# usb.net
KiCad netlist of a schematic drawn in EAGLE
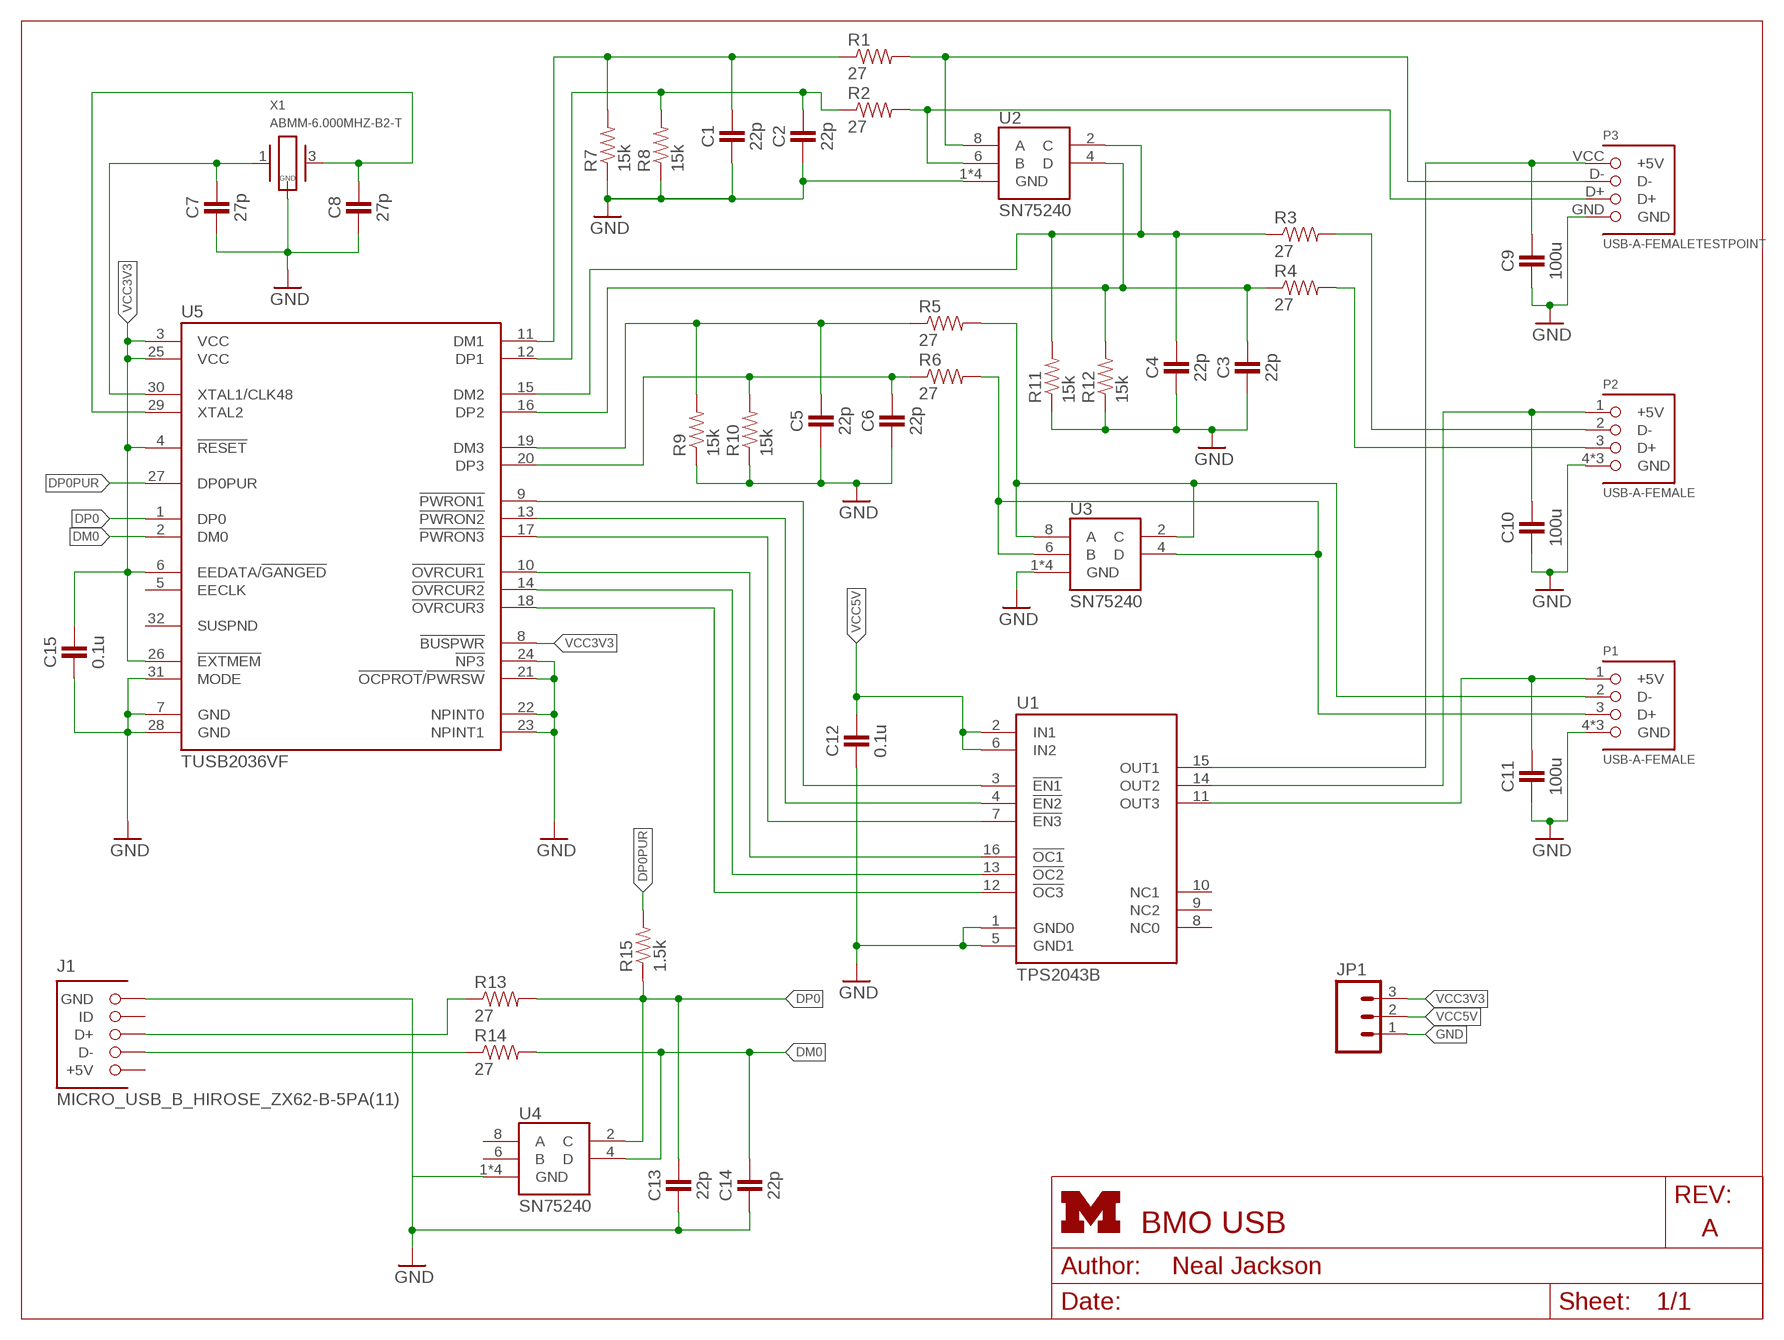
[diagram p0: schematic, sheet 1]

(export (version "E")
  (design (tool "Eeschema 10.0.6"))
  (components
    (comp (ref "C1")
      (value "22p")
      (footprint "eagle-import:0402_CAP")
      (libsource (lib "eagle-import") (part "CAPACITOR"))
    )
    (comp (ref "C2")
      (value "22p")
      (footprint "eagle-import:0402_CAP")
      (libsource (lib "eagle-import") (part "CAPACITOR"))
    )
    (comp (ref "C3")
      (value "22p")
      (footprint "eagle-import:0402_CAP")
      (libsource (lib "eagle-import") (part "CAPACITOR"))
    )
    (comp (ref "C4")
      (value "22p")
      (footprint "eagle-import:0402_CAP")
      (libsource (lib "eagle-import") (part "CAPACITOR"))
    )
    (comp (ref "C5")
      (value "22p")
      (footprint "eagle-import:0402_CAP")
      (libsource (lib "eagle-import") (part "CAPACITOR"))
    )
    (comp (ref "C6")
      (value "22p")
      (footprint "eagle-import:0402_CAP")
      (libsource (lib "eagle-import") (part "CAPACITOR"))
    )
    (comp (ref "C7")
      (value "27p")
      (footprint "eagle-import:0402_CAP")
      (libsource (lib "eagle-import") (part "CAPACITOR"))
    )
    (comp (ref "C8")
      (value "27p")
      (footprint "eagle-import:0402_CAP")
      (libsource (lib "eagle-import") (part "CAPACITOR"))
    )
    (comp (ref "C9")
      (value "100u")
      (footprint "eagle-import:0402_CAP")
      (libsource (lib "eagle-import") (part "CAPACITOR"))
    )
    (comp (ref "C10")
      (value "100u")
      (footprint "eagle-import:0402_CAP")
      (libsource (lib "eagle-import") (part "CAPACITOR"))
    )
    (comp (ref "C11")
      (value "100u")
      (footprint "eagle-import:0402_CAP")
      (libsource (lib "eagle-import") (part "CAPACITOR"))
    )
    (comp (ref "C12")
      (value "0.1u")
      (footprint "eagle-import:0402_CAP")
      (libsource (lib "eagle-import") (part "CAPACITOR"))
    )
    (comp (ref "C13")
      (value "22p")
      (footprint "eagle-import:0402_CAP")
      (libsource (lib "eagle-import") (part "CAPACITOR"))
    )
    (comp (ref "C14")
      (value "22p")
      (footprint "eagle-import:0402_CAP")
      (libsource (lib "eagle-import") (part "CAPACITOR"))
    )
    (comp (ref "C15")
      (value "0.1u")
      (footprint "eagle-import:0402_CAP")
      (libsource (lib "eagle-import") (part "CAPACITOR"))
    )
    (comp (ref "J1")
      (value "MICRO_USB_B_HIROSE_ZX62-B-5PA(11)")
      (footprint "eagle-import:USB_MICRO_B-HIROSE-ZX62-B-5PA(11)")
      (libsource (lib "eagle-import") (part "MICRO_USB_B_HIROSE_ZX62-B-5PA(11)"))
    )
    (comp (ref "JP1")
      (value "M03PTH")
      (footprint "eagle-import:1X03")
      (libsource (lib "eagle-import") (part "M03PTH"))
    )
    (comp (ref "P1")
      (value "USB-A-FEMALE")
      (footprint "eagle-import:87583-3010RPALF")
      (libsource (lib "eagle-import") (part "USB-A-FEMALE"))
    )
    (comp (ref "P2")
      (value "USB-A-FEMALE")
      (footprint "eagle-import:87583-3010RPALF")
      (libsource (lib "eagle-import") (part "USB-A-FEMALE"))
    )
    (comp (ref "P3")
      (value "USB-A-FEMALETESTPOINT")
      (footprint "eagle-import:USB-A-TESTPOINT")
      (libsource (lib "eagle-import") (part "USB-A-FEMALETESTPOINT"))
    )
    (comp (ref "R1")
      (value "27")
      (footprint "eagle-import:0402_RES")
      (libsource (lib "eagle-import") (part "RESISTOR0402_RES"))
    )
    (comp (ref "R2")
      (value "27")
      (footprint "eagle-import:0402_RES")
      (libsource (lib "eagle-import") (part "RESISTOR0402_RES"))
    )
    (comp (ref "R3")
      (value "27")
      (footprint "eagle-import:0402_RES")
      (libsource (lib "eagle-import") (part "RESISTOR0402_RES"))
    )
    (comp (ref "R4")
      (value "27")
      (footprint "eagle-import:0402_RES")
      (libsource (lib "eagle-import") (part "RESISTOR0402_RES"))
    )
    (comp (ref "R5")
      (value "27")
      (footprint "eagle-import:0402_RES")
      (libsource (lib "eagle-import") (part "RESISTOR0402_RES"))
    )
    (comp (ref "R6")
      (value "27")
      (footprint "eagle-import:0402_RES")
      (libsource (lib "eagle-import") (part "RESISTOR0402_RES"))
    )
    (comp (ref "R7")
      (value "15k")
      (footprint "eagle-import:0402_RES")
      (libsource (lib "eagle-import") (part "RESISTOR0402_RES"))
    )
    (comp (ref "R8")
      (value "15k")
      (footprint "eagle-import:0402_RES")
      (libsource (lib "eagle-import") (part "RESISTOR0402_RES"))
    )
    (comp (ref "R9")
      (value "15k")
      (footprint "eagle-import:0402_RES")
      (libsource (lib "eagle-import") (part "RESISTOR0402_RES"))
    )
    (comp (ref "R10")
      (value "15k")
      (footprint "eagle-import:0402_RES")
      (libsource (lib "eagle-import") (part "RESISTOR0402_RES"))
    )
    (comp (ref "R11")
      (value "15k")
      (footprint "eagle-import:0402_RES")
      (libsource (lib "eagle-import") (part "RESISTOR0402_RES"))
    )
    (comp (ref "R12")
      (value "15k")
      (footprint "eagle-import:0402_RES")
      (libsource (lib "eagle-import") (part "RESISTOR0402_RES"))
    )
    (comp (ref "R13")
      (value "27")
      (footprint "eagle-import:0402_RES")
      (libsource (lib "eagle-import") (part "RESISTOR0402_RES"))
    )
    (comp (ref "R14")
      (value "27")
      (footprint "eagle-import:0402_RES")
      (libsource (lib "eagle-import") (part "RESISTOR0402_RES"))
    )
    (comp (ref "R15")
      (value "1.5k")
      (footprint "eagle-import:0402_RES")
      (libsource (lib "eagle-import") (part "RESISTOR0402_RES"))
    )
    (comp (ref "U1")
      (value "TPS2043B")
      (footprint "eagle-import:SO16")
      (libsource (lib "eagle-import") (part "TPS2043B"))
    )
    (comp (ref "U2")
      (value "SN75240")
      (footprint "eagle-import:TSSOP8")
      (libsource (lib "eagle-import") (part "SN75240"))
    )
    (comp (ref "U3")
      (value "SN75240")
      (footprint "eagle-import:TSSOP8")
      (libsource (lib "eagle-import") (part "SN75240"))
    )
    (comp (ref "U4")
      (value "SN75240")
      (footprint "eagle-import:TSSOP8")
      (libsource (lib "eagle-import") (part "SN75240"))
    )
    (comp (ref "U5")
      (value "TUSB2036VF")
      (footprint "eagle-import:VF_S-PQFP-G32")
      (libsource (lib "eagle-import") (part "TUSB2036VF"))
    )
    (comp (ref "X1")
      (value "ABMM-6.000MHZ-B2-T")
      (footprint "eagle-import:ABMM-6.000MHZ-B2-T")
      (libsource (lib "eagle-import") (part "ABMM-6.000MHZ-B2-T"))
    )
  )
  (nets
    (net (code "1") (name "DM0") (class "Default")
      (node (ref "C14") (pin "1") (pinfunction "1_1") (pintype "bidirectional"))
      (node (ref "R14") (pin "2") (pinfunction "2_2") (pintype "passive"))
      (node (ref "U4") (pin "4") (pinfunction "D_4") (pintype "bidirectional"))
      (node (ref "U5") (pin "2") (pinfunction "DM0_2") (pintype "bidirectional"))
    )
    (net (code "2") (name "DP0") (class "Default")
      (node (ref "C13") (pin "1") (pinfunction "1_1") (pintype "bidirectional"))
      (node (ref "R13") (pin "2") (pinfunction "2_2") (pintype "passive"))
      (node (ref "R15") (pin "1") (pinfunction "1_1") (pintype "passive"))
      (node (ref "U4") (pin "2") (pinfunction "C_2") (pintype "bidirectional"))
      (node (ref "U5") (pin "1") (pinfunction "DP0_1") (pintype "bidirectional"))
    )
    (net (code "3") (name "DP0PUR") (class "Default")
      (node (ref "R15") (pin "2") (pinfunction "2_2") (pintype "passive"))
      (node (ref "U5") (pin "27") (pinfunction "DP0PUR_27") (pintype "output"))
    )
    (net (code "4") (name "GND") (class "Default")
      (node (ref "C1") (pin "2") (pinfunction "2_2") (pintype "bidirectional"))
      (node (ref "C10") (pin "2") (pinfunction "2_2") (pintype "bidirectional"))
      (node (ref "C11") (pin "2") (pinfunction "2_2") (pintype "bidirectional"))
      (node (ref "C12") (pin "2") (pinfunction "2_2") (pintype "bidirectional"))
      (node (ref "C13") (pin "2") (pinfunction "2_2") (pintype "bidirectional"))
      (node (ref "C14") (pin "2") (pinfunction "2_2") (pintype "bidirectional"))
      (node (ref "C15") (pin "2") (pinfunction "2_2") (pintype "bidirectional"))
      (node (ref "C2") (pin "2") (pinfunction "2_2") (pintype "bidirectional"))
      (node (ref "C3") (pin "2") (pinfunction "2_2") (pintype "bidirectional"))
      (node (ref "C4") (pin "2") (pinfunction "2_2") (pintype "bidirectional"))
      (node (ref "C5") (pin "2") (pinfunction "2_2") (pintype "bidirectional"))
      (node (ref "C6") (pin "2") (pinfunction "2_2") (pintype "bidirectional"))
      (node (ref "C7") (pin "2") (pinfunction "2_2") (pintype "bidirectional"))
      (node (ref "C8") (pin "2") (pinfunction "2_2") (pintype "bidirectional"))
      (node (ref "C9") (pin "2") (pinfunction "2_2") (pintype "bidirectional"))
      (node (ref "J1") (pin "5") (pinfunction "GND_5") (pintype "bidirectional"))
      (node (ref "JP1") (pin "1") (pinfunction "1_1") (pintype "passive"))
      (node (ref "P1") (pin "4") (pinfunction "GND_4") (pintype "bidirectional"))
      (node (ref "P1") (pin "P$1") (pinfunction "GND_P$1") (pintype "bidirectional"))
      (node (ref "P1") (pin "P$2") (pinfunction "GND_P$2") (pintype "bidirectional"))
      (node (ref "P2") (pin "4") (pinfunction "GND_4") (pintype "bidirectional"))
      (node (ref "P2") (pin "P$1") (pinfunction "GND_P$1") (pintype "bidirectional"))
      (node (ref "P2") (pin "P$2") (pinfunction "GND_P$2") (pintype "bidirectional"))
      (node (ref "P3") (pin "GND") (pinfunction "GND_GND") (pintype "bidirectional"))
      (node (ref "R10") (pin "1") (pinfunction "1_1") (pintype "passive"))
      (node (ref "R11") (pin "1") (pinfunction "1_1") (pintype "passive"))
      (node (ref "R12") (pin "1") (pinfunction "1_1") (pintype "passive"))
      (node (ref "R7") (pin "1") (pinfunction "1_1") (pintype "passive"))
      (node (ref "R8") (pin "1") (pinfunction "1_1") (pintype "passive"))
      (node (ref "R9") (pin "1") (pinfunction "1_1") (pintype "passive"))
      (node (ref "U1") (pin "1") (pinfunction "GND0_1") (pintype "bidirectional"))
      (node (ref "U1") (pin "5") (pinfunction "GND1_5") (pintype "bidirectional"))
      (node (ref "U2") (pin "1") (pinfunction "GND_1") (pintype "bidirectional"))
      (node (ref "U2") (pin "3") (pinfunction "GND_3") (pintype "bidirectional"))
      (node (ref "U2") (pin "5") (pinfunction "GND_5") (pintype "bidirectional"))
      (node (ref "U2") (pin "7") (pinfunction "GND_7") (pintype "bidirectional"))
      (node (ref "U3") (pin "1") (pinfunction "GND_1") (pintype "bidirectional"))
      (node (ref "U3") (pin "3") (pinfunction "GND_3") (pintype "bidirectional"))
      (node (ref "U3") (pin "5") (pinfunction "GND_5") (pintype "bidirectional"))
      (node (ref "U3") (pin "7") (pinfunction "GND_7") (pintype "bidirectional"))
      (node (ref "U4") (pin "1") (pinfunction "GND_1") (pintype "bidirectional"))
      (node (ref "U4") (pin "3") (pinfunction "GND_3") (pintype "bidirectional"))
      (node (ref "U4") (pin "5") (pinfunction "GND_5") (pintype "bidirectional"))
      (node (ref "U4") (pin "7") (pinfunction "GND_7") (pintype "bidirectional"))
      (node (ref "U5") (pin "21") (pinfunction "~{OCPROT}/~{PWRSW}_21") (pintype "input"))
      (node (ref "U5") (pin "22") (pinfunction "NPINT0_22") (pintype "input"))
      (node (ref "U5") (pin "23") (pinfunction "NPINT1_23") (pintype "input"))
      (node (ref "U5") (pin "24") (pinfunction "~{NP3}_24") (pintype "input"))
      (node (ref "U5") (pin "28") (pinfunction "GND_28") (pintype "power_in"))
      (node (ref "U5") (pin "31") (pinfunction "MODE_31") (pintype "input"))
      (node (ref "U5") (pin "7") (pinfunction "GND_7") (pintype "power_in"))
      (node (ref "X1") (pin "2") (pinfunction "GND_2") (pintype "bidirectional"))
      (node (ref "X1") (pin "4") (pinfunction "GND_4") (pintype "bidirectional"))
    )
    (net (code "5") (name "Net-(J1-D+)") (class "Default")
      (node (ref "J1") (pin "3") (pinfunction "D+_3") (pintype "bidirectional"))
      (node (ref "R13") (pin "1") (pinfunction "1_1") (pintype "passive"))
    )
    (net (code "6") (name "Net-(J1-D-)") (class "Default")
      (node (ref "J1") (pin "2") (pinfunction "D-_2") (pintype "bidirectional"))
      (node (ref "R14") (pin "1") (pinfunction "1_1") (pintype "passive"))
    )
    (net (code "7") (name "Net-(P1-+5V)") (class "Default")
      (node (ref "C11") (pin "1") (pinfunction "1_1") (pintype "bidirectional"))
      (node (ref "P1") (pin "1") (pinfunction "+5V_1") (pintype "bidirectional"))
      (node (ref "U1") (pin "11") (pinfunction "OUT3_11") (pintype "bidirectional"))
    )
    (net (code "8") (name "Net-(P1-D+)") (class "Default")
      (node (ref "P1") (pin "3") (pinfunction "D+_3") (pintype "bidirectional"))
      (node (ref "R6") (pin "2") (pinfunction "2_2") (pintype "passive"))
      (node (ref "U3") (pin "4") (pinfunction "D_4") (pintype "bidirectional"))
      (node (ref "U3") (pin "6") (pinfunction "B_6") (pintype "bidirectional"))
    )
    (net (code "9") (name "Net-(P1-D-)") (class "Default")
      (node (ref "P1") (pin "2") (pinfunction "D-_2") (pintype "bidirectional"))
      (node (ref "R5") (pin "2") (pinfunction "2_2") (pintype "passive"))
      (node (ref "U3") (pin "2") (pinfunction "C_2") (pintype "bidirectional"))
      (node (ref "U3") (pin "8") (pinfunction "A_8") (pintype "bidirectional"))
    )
    (net (code "10") (name "Net-(P2-+5V)") (class "Default")
      (node (ref "C10") (pin "1") (pinfunction "1_1") (pintype "bidirectional"))
      (node (ref "P2") (pin "1") (pinfunction "+5V_1") (pintype "bidirectional"))
      (node (ref "U1") (pin "14") (pinfunction "OUT2_14") (pintype "bidirectional"))
    )
    (net (code "11") (name "Net-(P2-D+)") (class "Default")
      (node (ref "P2") (pin "3") (pinfunction "D+_3") (pintype "bidirectional"))
      (node (ref "R4") (pin "2") (pinfunction "2_2") (pintype "passive"))
    )
    (net (code "12") (name "Net-(P2-D-)") (class "Default")
      (node (ref "P2") (pin "2") (pinfunction "D-_2") (pintype "bidirectional"))
      (node (ref "R3") (pin "2") (pinfunction "2_2") (pintype "passive"))
    )
    (net (code "13") (name "Net-(P3-+5V)") (class "Default")
      (node (ref "C9") (pin "1") (pinfunction "1_1") (pintype "bidirectional"))
      (node (ref "P3") (pin "VCC") (pinfunction "+5V_VCC") (pintype "bidirectional"))
      (node (ref "U1") (pin "15") (pinfunction "OUT1_15") (pintype "bidirectional"))
    )
    (net (code "14") (name "Net-(U1-~{EN1})") (class "Default")
      (node (ref "U1") (pin "3") (pinfunction "~{EN1}_3") (pintype "bidirectional"))
      (node (ref "U5") (pin "9") (pinfunction "~{PWRON1}_9") (pintype "output"))
    )
    (net (code "15") (name "Net-(U1-~{EN2})") (class "Default")
      (node (ref "U1") (pin "4") (pinfunction "~{EN2}_4") (pintype "bidirectional"))
      (node (ref "U5") (pin "13") (pinfunction "~{PWRON2}_13") (pintype "output"))
    )
    (net (code "16") (name "Net-(U1-~{EN3})") (class "Default")
      (node (ref "U1") (pin "7") (pinfunction "~{EN3}_7") (pintype "bidirectional"))
      (node (ref "U5") (pin "17") (pinfunction "~{PWRON3}_17") (pintype "output"))
    )
    (net (code "17") (name "Net-(U1-~{OC1})") (class "Default")
      (node (ref "U1") (pin "16") (pinfunction "~{OC1}_16") (pintype "bidirectional"))
      (node (ref "U5") (pin "10") (pinfunction "~{OVRCUR1}_10") (pintype "input"))
    )
    (net (code "18") (name "Net-(U1-~{OC2})") (class "Default")
      (node (ref "U1") (pin "13") (pinfunction "~{OC2}_13") (pintype "bidirectional"))
      (node (ref "U5") (pin "14") (pinfunction "~{OVRCUR2}_14") (pintype "input"))
    )
    (net (code "19") (name "Net-(U1-~{OC3})") (class "Default")
      (node (ref "U1") (pin "12") (pinfunction "~{OC3}_12") (pintype "bidirectional"))
      (node (ref "U5") (pin "18") (pinfunction "~{OVRCUR3}_18") (pintype "input"))
    )
    (net (code "20") (name "Net-(U2-A)") (class "Default")
      (node (ref "P3") (pin "D-") (pinfunction "D-_D-") (pintype "bidirectional"))
      (node (ref "R1") (pin "2") (pinfunction "2_2") (pintype "passive"))
      (node (ref "U2") (pin "8") (pinfunction "A_8") (pintype "bidirectional"))
    )
    (net (code "21") (name "Net-(U2-B)") (class "Default")
      (node (ref "P3") (pin "D+") (pinfunction "D+_D+") (pintype "bidirectional"))
      (node (ref "R2") (pin "2") (pinfunction "2_2") (pintype "passive"))
      (node (ref "U2") (pin "6") (pinfunction "B_6") (pintype "bidirectional"))
    )
    (net (code "22") (name "Net-(U2-C)") (class "Default")
      (node (ref "C4") (pin "1") (pinfunction "1_1") (pintype "bidirectional"))
      (node (ref "R11") (pin "2") (pinfunction "2_2") (pintype "passive"))
      (node (ref "R3") (pin "1") (pinfunction "1_1") (pintype "passive"))
      (node (ref "U2") (pin "2") (pinfunction "C_2") (pintype "bidirectional"))
      (node (ref "U5") (pin "15") (pinfunction "DM2_15") (pintype "bidirectional"))
    )
    (net (code "23") (name "Net-(U2-D)") (class "Default")
      (node (ref "C3") (pin "1") (pinfunction "1_1") (pintype "bidirectional"))
      (node (ref "R12") (pin "2") (pinfunction "2_2") (pintype "passive"))
      (node (ref "R4") (pin "1") (pinfunction "1_1") (pintype "passive"))
      (node (ref "U2") (pin "4") (pinfunction "D_4") (pintype "bidirectional"))
      (node (ref "U5") (pin "16") (pinfunction "DP2_16") (pintype "bidirectional"))
    )
    (net (code "24") (name "Net-(U5-DM1)") (class "Default")
      (node (ref "C1") (pin "1") (pinfunction "1_1") (pintype "bidirectional"))
      (node (ref "R1") (pin "1") (pinfunction "1_1") (pintype "passive"))
      (node (ref "R7") (pin "2") (pinfunction "2_2") (pintype "passive"))
      (node (ref "U5") (pin "11") (pinfunction "DM1_11") (pintype "bidirectional"))
    )
    (net (code "25") (name "Net-(U5-DM3)") (class "Default")
      (node (ref "C5") (pin "1") (pinfunction "1_1") (pintype "bidirectional"))
      (node (ref "R5") (pin "1") (pinfunction "1_1") (pintype "passive"))
      (node (ref "R9") (pin "2") (pinfunction "2_2") (pintype "passive"))
      (node (ref "U5") (pin "19") (pinfunction "DM3_19") (pintype "bidirectional"))
    )
    (net (code "26") (name "Net-(U5-DP1)") (class "Default")
      (node (ref "C2") (pin "1") (pinfunction "1_1") (pintype "bidirectional"))
      (node (ref "R2") (pin "1") (pinfunction "1_1") (pintype "passive"))
      (node (ref "R8") (pin "2") (pinfunction "2_2") (pintype "passive"))
      (node (ref "U5") (pin "12") (pinfunction "DP1_12") (pintype "bidirectional"))
    )
    (net (code "27") (name "Net-(U5-DP3)") (class "Default")
      (node (ref "C6") (pin "1") (pinfunction "1_1") (pintype "bidirectional"))
      (node (ref "R10") (pin "2") (pinfunction "2_2") (pintype "passive"))
      (node (ref "R6") (pin "1") (pinfunction "1_1") (pintype "passive"))
      (node (ref "U5") (pin "20") (pinfunction "DP3_20") (pintype "bidirectional"))
    )
    (net (code "28") (name "Net-(U5-XTAL1{slash}CLK48)") (class "Default")
      (node (ref "C7") (pin "1") (pinfunction "1_1") (pintype "bidirectional"))
      (node (ref "U5") (pin "30") (pinfunction "XTAL1/CLK48_30") (pintype "input"))
      (node (ref "X1") (pin "1") (pinfunction "1_1") (pintype "bidirectional"))
    )
    (net (code "29") (name "Net-(U5-XTAL2)") (class "Default")
      (node (ref "C8") (pin "1") (pinfunction "1_1") (pintype "bidirectional"))
      (node (ref "U5") (pin "29") (pinfunction "XTAL2_29") (pintype "output"))
      (node (ref "X1") (pin "3") (pinfunction "2_3") (pintype "bidirectional"))
    )
    (net (code "30") (name "VCC3V3") (class "Default")
      (node (ref "C15") (pin "1") (pinfunction "1_1") (pintype "bidirectional"))
      (node (ref "JP1") (pin "3") (pinfunction "3_3") (pintype "passive"))
      (node (ref "U5") (pin "25") (pinfunction "VCC_25") (pintype "power_in"))
      (node (ref "U5") (pin "26") (pinfunction "~{EXTMEM}_26") (pintype "input"))
      (node (ref "U5") (pin "3") (pinfunction "VCC_3") (pintype "power_in"))
      (node (ref "U5") (pin "4") (pinfunction "~{RESET}_4") (pintype "input"))
      (node (ref "U5") (pin "6") (pinfunction "EEDATA/~{GANGED}_6") (pintype "bidirectional"))
      (node (ref "U5") (pin "8") (pinfunction "~{BUSPWR}_8") (pintype "input"))
    )
    (net (code "31") (name "VCC5V") (class "Default")
      (node (ref "C12") (pin "1") (pinfunction "1_1") (pintype "bidirectional"))
      (node (ref "JP1") (pin "2") (pinfunction "2_2") (pintype "passive"))
      (node (ref "U1") (pin "2") (pinfunction "IN1_2") (pintype "bidirectional"))
      (node (ref "U1") (pin "6") (pinfunction "IN2_6") (pintype "bidirectional"))
    )
    (net (code "32") (name "unconnected-(J1-+5V-Pad1)") (class "Default")
      (node (ref "J1") (pin "1") (pinfunction "+5V_1") (pintype "bidirectional"))
    )
    (net (code "33") (name "unconnected-(J1-ID-Pad4)") (class "Default")
      (node (ref "J1") (pin "4") (pinfunction "ID_4") (pintype "bidirectional"))
    )
    (net (code "34") (name "unconnected-(U1-NC0-Pad8)") (class "Default")
      (node (ref "U1") (pin "8") (pinfunction "NC0_8") (pintype "bidirectional"))
    )
    (net (code "35") (name "unconnected-(U1-NC1-Pad10)") (class "Default")
      (node (ref "U1") (pin "10") (pinfunction "NC1_10") (pintype "bidirectional"))
    )
    (net (code "36") (name "unconnected-(U1-NC2-Pad9)") (class "Default")
      (node (ref "U1") (pin "9") (pinfunction "NC2_9") (pintype "bidirectional"))
    )
    (net (code "37") (name "unconnected-(U4-A-Pad8)") (class "Default")
      (node (ref "U4") (pin "8") (pinfunction "A_8") (pintype "bidirectional"))
    )
    (net (code "38") (name "unconnected-(U4-B-Pad6)") (class "Default")
      (node (ref "U4") (pin "6") (pinfunction "B_6") (pintype "bidirectional"))
    )
    (net (code "39") (name "unconnected-(U5-EECLK-Pad5)") (class "Default")
      (node (ref "U5") (pin "5") (pinfunction "EECLK_5") (pintype "output"))
    )
    (net (code "40") (name "unconnected-(U5-SUSPND-Pad32)") (class "Default")
      (node (ref "U5") (pin "32") (pinfunction "SUSPND_32") (pintype "output"))
    )
  )
)
